# OSC.net
KiCad netlist of a schematic drawn in Altium Designer
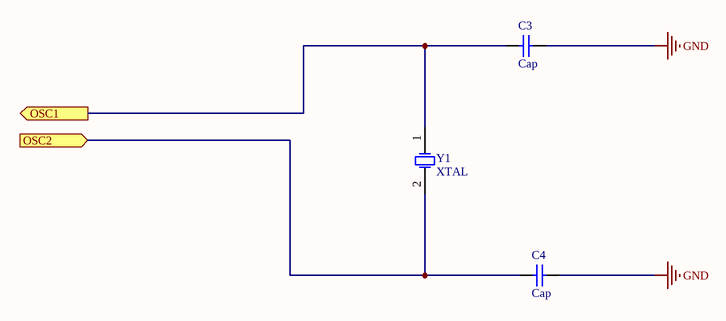
[diagram p0: OSC.SchDoc]

(export (version "E")
  (design (tool "Eeschema 10.0.6"))
  (components
    (comp (ref "C3")
      (value "Cap")
      (footprint "RAD-0.3")
      (description "Capacitor")
      (fields (field (name "PUBLISHER") "Altium Limited"))
      (libsource (lib "Miscellaneous Devices") (part "Cap"))
    )
    (comp (ref "C4")
      (value "Cap")
      (footprint "RAD-0.3")
      (description "Capacitor")
      (fields (field (name "PUBLISHER") "Altium Limited"))
      (libsource (lib "Miscellaneous Devices") (part "Cap"))
    )
    (comp (ref "Y1")
      (value "XTAL")
      (footprint "R38")
      (description "Crystal Oscillator")
      (fields (field (name "PUBLISHER") "Altium Limited"))
      (libsource (lib "Miscellaneous Devices") (part "XTAL"))
    )
  )
  (nets
    (net (code "1") (name "/OSC1") (class "Default")
      (node (ref "C3") (pin "1") (pinfunction "1_1") (pintype "passive"))
      (node (ref "Y1") (pin "1") (pinfunction "OSC1_1") (pintype "passive"))
    )
    (net (code "2") (name "/OSC2") (class "Default")
      (node (ref "C4") (pin "1") (pinfunction "1_1") (pintype "passive"))
      (node (ref "Y1") (pin "2") (pinfunction "OSC2_2") (pintype "passive"))
    )
    (net (code "3") (name "GND") (class "Default")
      (node (ref "C3") (pin "2") (pinfunction "2_2") (pintype "passive"))
      (node (ref "C4") (pin "2") (pinfunction "2_2") (pintype "passive"))
    )
  )
)
